# WunderBar_v102b.net
KiCad netlist of a schematic drawn in Altium Designer
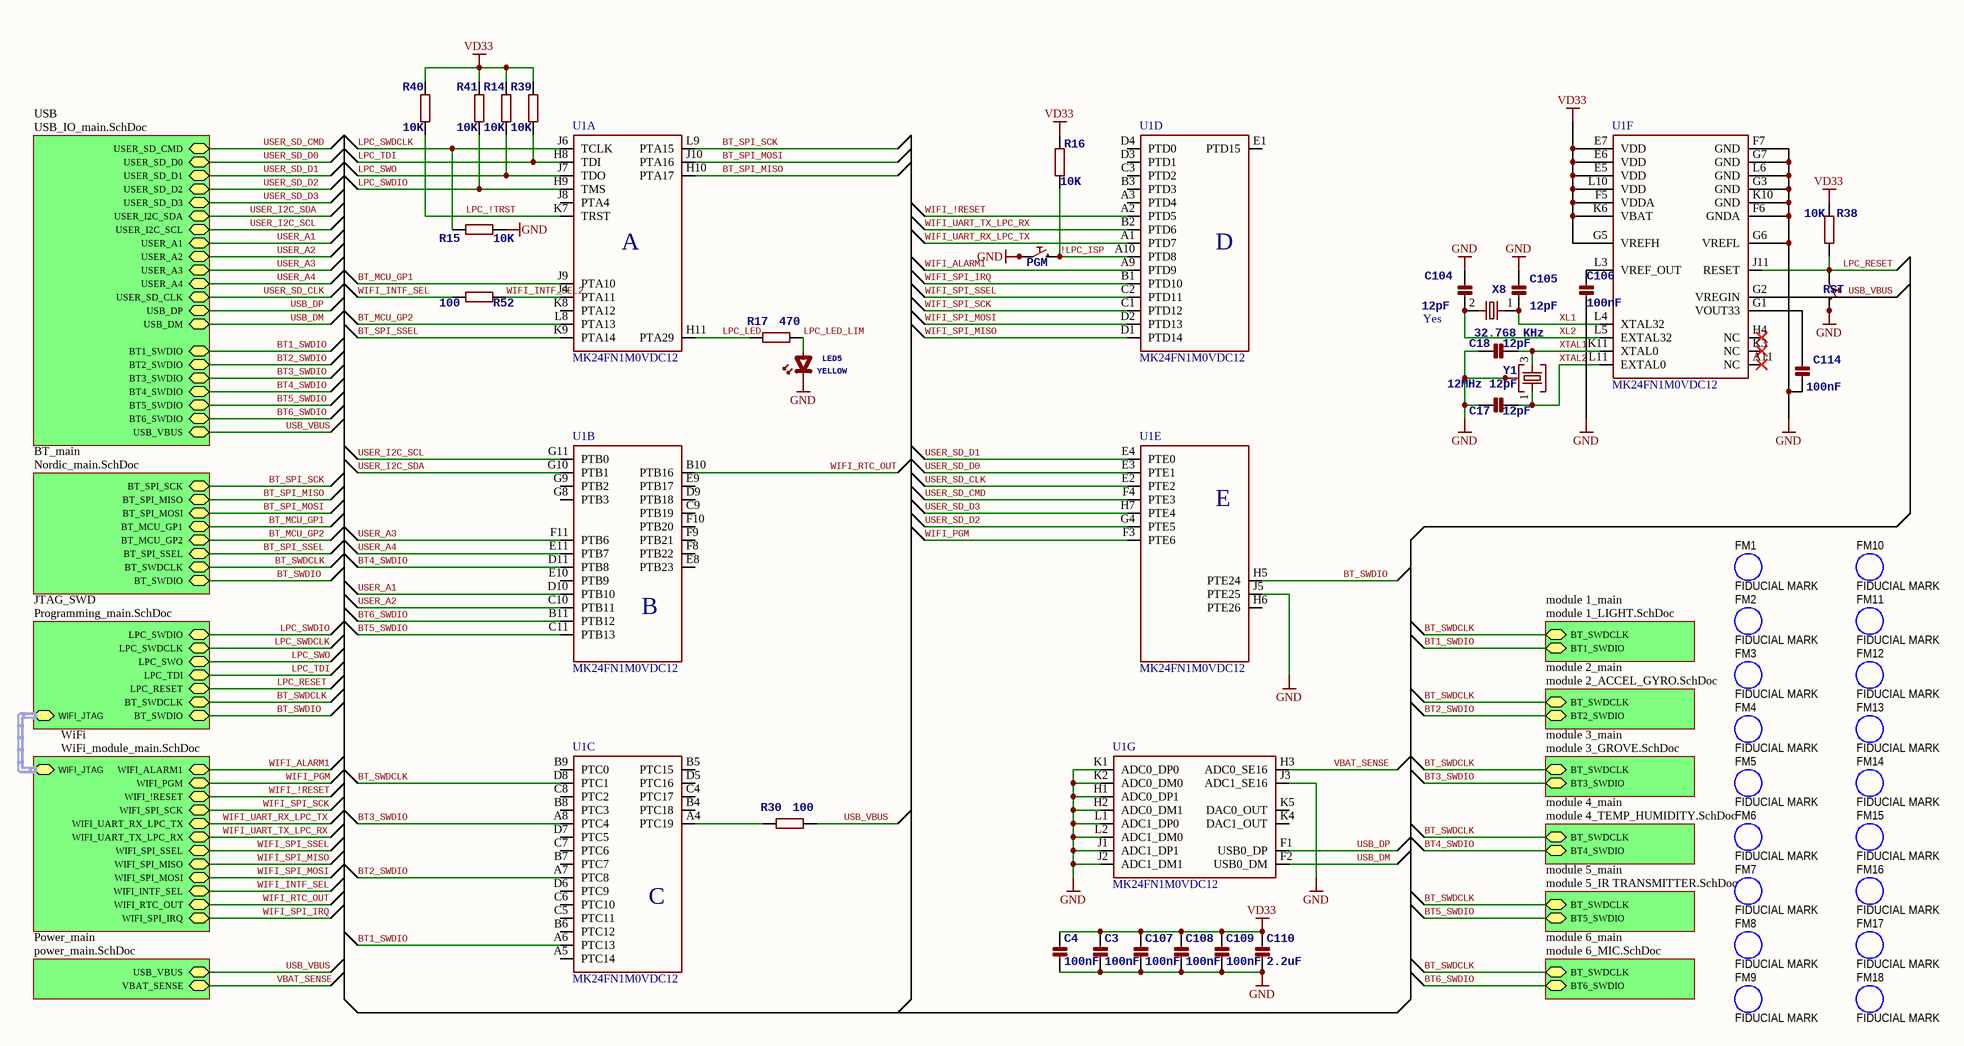
[diagram p0: WunderBar_v102b.SchDoc]

(export (version "E")
  (design (tool "Eeschema 10.0.6"))
  (components
    (comp (ref "C3")
      (value "100nF")
      (footprint "0402")
      (description "Ceramic capacitor")
      (libsource (lib "WunderBar_v101") (part "CAP_CERAMIC0402"))
    )
    (comp (ref "C4")
      (value "100nF")
      (footprint "0402")
      (description "Ceramic capacitor")
      (libsource (lib "WunderBar_v101") (part "CAP_CERAMIC0402"))
    )
    (comp (ref "C17")
      (value "12pF")
      (footprint "0402")
      (description "Ceramic capacitor")
      (libsource (lib "WunderBar_v101") (part "CAP_CERAMIC0402"))
    )
    (comp (ref "C18")
      (value "12pF")
      (footprint "0402")
      (description "Ceramic capacitor")
      (libsource (lib "WunderBar_v101") (part "CAP_CERAMIC0402"))
    )
    (comp (ref "C104")
      (value "12pF")
      (footprint "0402")
      (description "Ceramic capacitor")
      (fields (field (name "SMD") "Yes"))
      (libsource (lib "") (part "CAP_CERAMIC0402_1"))
    )
    (comp (ref "C105")
      (value "12pF")
      (footprint "0402")
      (description "Ceramic capacitor")
      (libsource (lib "") (part "CAP_CERAMIC0402_1"))
    )
    (comp (ref "C106")
      (value "100nF")
      (footprint "0402")
      (description "Ceramic capacitor")
      (libsource (lib "WunderBar_v101") (part "CAP_CERAMIC0402"))
    )
    (comp (ref "C107")
      (value "100nF")
      (footprint "0402")
      (description "Ceramic capacitor")
      (libsource (lib "WunderBar_v101") (part "CAP_CERAMIC0402"))
    )
    (comp (ref "C108")
      (value "100nF")
      (footprint "0402")
      (description "Ceramic capacitor")
      (libsource (lib "WunderBar_v101") (part "CAP_CERAMIC0402"))
    )
    (comp (ref "C109")
      (value "100nF")
      (footprint "0402")
      (description "Ceramic capacitor")
      (libsource (lib "WunderBar_v101") (part "CAP_CERAMIC0402"))
    )
    (comp (ref "C110")
      (value "2.2uF")
      (footprint "0603")
      (description "Ceramic capacitor")
      (libsource (lib "WunderBar_v101") (part "CAP_CERAMIC0402"))
    )
    (comp (ref "C114")
      (value "100nF")
      (footprint "0402")
      (description "Ceramic capacitor")
      (libsource (lib "") (part "CAP_CERAMIC0402_1"))
    )
    (comp (ref "FM1")
      (value "FIDUCIAL MARK")
      (footprint "FIDUCIAL MARK 0.6MM")
      (description "Fiducial Mark")
      (libsource (lib "WunderBar_v101") (part "FIDUCIAL MARK"))
    )
    (comp (ref "FM2")
      (value "FIDUCIAL MARK")
      (footprint "FIDUCIAL MARK 0.6MM")
      (description "Fiducial Mark")
      (libsource (lib "WunderBar_v101") (part "FIDUCIAL MARK"))
    )
    (comp (ref "FM3")
      (value "FIDUCIAL MARK")
      (footprint "FIDUCIAL MARK 0.6MM")
      (description "Fiducial Mark")
      (libsource (lib "WunderBar_v101") (part "FIDUCIAL MARK"))
    )
    (comp (ref "FM4")
      (value "FIDUCIAL MARK")
      (footprint "FIDUCIAL MARK 0.6MM")
      (description "Fiducial Mark")
      (libsource (lib "WunderBar_v101") (part "FIDUCIAL MARK"))
    )
    (comp (ref "FM5")
      (value "FIDUCIAL MARK")
      (footprint "FIDUCIAL MARK 0.6MM")
      (description "Fiducial Mark")
      (libsource (lib "WunderBar_v101") (part "FIDUCIAL MARK"))
    )
    (comp (ref "FM6")
      (value "FIDUCIAL MARK")
      (footprint "FIDUCIAL MARK 0.6MM")
      (description "Fiducial Mark")
      (libsource (lib "WunderBar_v101") (part "FIDUCIAL MARK"))
    )
    (comp (ref "FM7")
      (value "FIDUCIAL MARK")
      (footprint "FIDUCIAL MARK 0.6MM")
      (description "Fiducial Mark")
      (libsource (lib "WunderBar_v101") (part "FIDUCIAL MARK"))
    )
    (comp (ref "FM8")
      (value "FIDUCIAL MARK")
      (footprint "FIDUCIAL MARK 0.6MM")
      (description "Fiducial Mark")
      (libsource (lib "WunderBar_v101") (part "FIDUCIAL MARK"))
    )
    (comp (ref "FM9")
      (value "FIDUCIAL MARK")
      (footprint "FIDUCIAL MARK 0.6MM")
      (description "Fiducial Mark")
      (libsource (lib "WunderBar_v101") (part "FIDUCIAL MARK"))
    )
    (comp (ref "FM10")
      (value "FIDUCIAL MARK")
      (footprint "FIDUCIAL MARK 0.6MM")
      (description "Fiducial Mark")
      (libsource (lib "WunderBar_v101") (part "FIDUCIAL MARK"))
    )
    (comp (ref "FM11")
      (value "FIDUCIAL MARK")
      (footprint "FIDUCIAL MARK 0.6MM")
      (description "Fiducial Mark")
      (libsource (lib "WunderBar_v101") (part "FIDUCIAL MARK"))
    )
    (comp (ref "FM12")
      (value "FIDUCIAL MARK")
      (footprint "FIDUCIAL MARK 0.6MM")
      (description "Fiducial Mark")
      (libsource (lib "WunderBar_v101") (part "FIDUCIAL MARK"))
    )
    (comp (ref "FM13")
      (value "FIDUCIAL MARK")
      (footprint "FIDUCIAL MARK 0.6MM")
      (description "Fiducial Mark")
      (libsource (lib "WunderBar_v101") (part "FIDUCIAL MARK"))
    )
    (comp (ref "FM14")
      (value "FIDUCIAL MARK")
      (footprint "FIDUCIAL MARK 0.6MM")
      (description "Fiducial Mark")
      (libsource (lib "WunderBar_v101") (part "FIDUCIAL MARK"))
    )
    (comp (ref "FM15")
      (value "FIDUCIAL MARK")
      (footprint "FIDUCIAL MARK 0.6MM")
      (description "Fiducial Mark")
      (libsource (lib "WunderBar_v101") (part "FIDUCIAL MARK"))
    )
    (comp (ref "FM16")
      (value "FIDUCIAL MARK")
      (footprint "FIDUCIAL MARK 0.6MM")
      (description "Fiducial Mark")
      (libsource (lib "WunderBar_v101") (part "FIDUCIAL MARK"))
    )
    (comp (ref "FM17")
      (value "FIDUCIAL MARK")
      (footprint "FIDUCIAL MARK 0.6MM")
      (description "Fiducial Mark")
      (libsource (lib "WunderBar_v101") (part "FIDUCIAL MARK"))
    )
    (comp (ref "FM18")
      (value "FIDUCIAL MARK")
      (footprint "FIDUCIAL MARK 0.6MM")
      (description "Fiducial Mark")
      (libsource (lib "WunderBar_v101") (part "FIDUCIAL MARK"))
    )
    (comp (ref "LED5")
      (value "YELLOW")
      (footprint "0402_POLAR")
      (description "LED common")
      (libsource (lib "WunderBar_v101") (part "LED0402"))
    )
    (comp (ref "PGM")
      (value "Tact Sw 4.6x2.8")
      (footprint "CK-KMR2")
      (description "Push button")
      (libsource (lib "WunderBar_v101") (part "PUSHBUTTONKMR2XX"))
    )
    (comp (ref "R14")
      (value "10K")
      (footprint "0402")
      (description "RESISTOR")
      (libsource (lib "WunderBar_v101") (part "R-EU_0402"))
    )
    (comp (ref "R15")
      (value "10K")
      (footprint "0402")
      (description "RESISTOR")
      (libsource (lib "WunderBar_v101") (part "R-EU_0402"))
    )
    (comp (ref "R16")
      (value "10K")
      (footprint "0402")
      (description "RESISTOR")
      (libsource (lib "WunderBar_v101") (part "R-EU_0402"))
    )
    (comp (ref "R17")
      (value "470")
      (footprint "0402")
      (description "RESISTOR")
      (libsource (lib "WunderBar_v101") (part "R-EU_0402"))
    )
    (comp (ref "R30")
      (value "100")
      (footprint "0402")
      (description "RESISTOR")
      (libsource (lib "WunderBar_v101") (part "R-EU_0402"))
    )
    (comp (ref "R38")
      (value "10K")
      (footprint "0402")
      (description "RESISTOR")
      (libsource (lib "WunderBar_v101") (part "R-EU_0402"))
    )
    (comp (ref "R39")
      (value "10K")
      (footprint "0402")
      (description "RESISTOR")
      (libsource (lib "WunderBar_v101") (part "R-EU_0402"))
    )
    (comp (ref "R40")
      (value "10K")
      (footprint "0402")
      (description "RESISTOR")
      (libsource (lib "WunderBar_v101") (part "R-EU_0402"))
    )
    (comp (ref "R41")
      (value "10K")
      (footprint "0402")
      (description "RESISTOR")
      (libsource (lib "WunderBar_v101") (part "R-EU_0402"))
    )
    (comp (ref "R52")
      (value "100")
      (footprint "0402")
      (description "RESISTOR")
      (libsource (lib "WunderBar_v101") (part "R-EU_0402"))
    )
    (comp (ref "RST")
      (value "Tact Sw 4.6x2.8")
      (footprint "CK-KMR2")
      (description "Push button")
      (libsource (lib "WunderBar_v101") (part "PUSHBUTTONKMR2XX"))
    )
    (comp (ref "U1")
      (value "MK24FN1M0VDC12")
      (footprint "BGA121-0.65")
      (description "MK24FN1M0VDC12 121-PIN BGA Microcontroller")
      (libsource (lib "WunderBar_v101") (part "MK24FN1M0VDC12"))
    )
    (comp (ref "X8")
      (value "32.768 KHz")
      (footprint "1206_MINIMELF_COMBO")
      (description "CL05C120JB5")
      (libsource (lib "WunderBar_v101") (part "CRYSTAL1206"))
    )
    (comp (ref "Y1")
      (value "12MHz 12pF")
      (footprint "ABM8G")
      (description "CX2520DB16000D0GEJCC")
      (libsource (lib "WunderBar_v101") (part "CRYSTAL_WITH_GROUNDABM8G"))
    )
  )
  (nets
    (net (code "1") (name "/!LPC_ISP") (class "Default")
      (node (ref "PGM") (pin "P3") (pinfunction "3_P3") (pintype "passive"))
      (node (ref "PGM") (pin "P4") (pinfunction "4_P4") (pintype "passive"))
      (node (ref "R16") (pin "1") (pinfunction "1_1") (pintype "passive"))
      (node (ref "U1") (pin "A10") (pinfunction "PTD8_A10") (pintype "passive"))
    )
    (net (code "2") (name "/BT1_SWDIO") (class "Default")
      (node (ref "U1") (pin "A6") (pinfunction "PTC13_A6") (pintype "passive"))
    )
    (net (code "3") (name "/BT2_SWDIO") (class "Default")
      (node (ref "U1") (pin "A7") (pinfunction "PTC8_A7") (pintype "passive"))
    )
    (net (code "4") (name "/BT3_SWDIO") (class "Default")
      (node (ref "U1") (pin "A8") (pinfunction "PTC4_A8") (pintype "passive"))
    )
    (net (code "5") (name "/BT4_SWDIO") (class "Default")
      (node (ref "U1") (pin "D11") (pinfunction "PTB8_D11") (pintype "passive"))
    )
    (net (code "6") (name "/BT5_SWDIO") (class "Default")
      (node (ref "U1") (pin "C11") (pinfunction "PTB13_C11") (pintype "passive"))
    )
    (net (code "7") (name "/BT6_SWDIO") (class "Default")
      (node (ref "U1") (pin "B11") (pinfunction "PTB12_B11") (pintype "passive"))
    )
    (net (code "8") (name "/BT_MCU_GP1") (class "Default")
      (node (ref "U1") (pin "J9") (pinfunction "PTA10_J9") (pintype "passive"))
    )
    (net (code "9") (name "/BT_MCU_GP2") (class "Default")
      (node (ref "U1") (pin "L8") (pinfunction "PTA13_L8") (pintype "passive"))
    )
    (net (code "10") (name "/BT_SPI_MISO") (class "Default")
      (node (ref "U1") (pin "H10") (pinfunction "PTA17_H10") (pintype "passive"))
    )
    (net (code "11") (name "/BT_SPI_MOSI") (class "Default")
      (node (ref "U1") (pin "J10") (pinfunction "PTA16_J10") (pintype "passive"))
    )
    (net (code "12") (name "/BT_SPI_SCK") (class "Default")
      (node (ref "U1") (pin "L9") (pinfunction "PTA15_L9") (pintype "passive"))
    )
    (net (code "13") (name "/BT_SPI_SSEL") (class "Default")
      (node (ref "U1") (pin "K9") (pinfunction "PTA14_K9") (pintype "passive"))
    )
    (net (code "14") (name "/BT_SWDCLK") (class "Default")
      (node (ref "U1") (pin "D8") (pinfunction "PTC1_D8") (pintype "passive"))
    )
    (net (code "15") (name "/BT_SWDIO") (class "Default")
      (node (ref "U1") (pin "H5") (pinfunction "PTE24_H5") (pintype "passive"))
    )
    (net (code "16") (name "/LPC_!TRST") (class "Default")
      (node (ref "R40") (pin "1") (pinfunction "1_1") (pintype "passive"))
      (node (ref "U1") (pin "K7") (pinfunction "TRST_K7") (pintype "passive"))
    )
    (net (code "17") (name "/LPC_LED") (class "Default")
      (node (ref "R17") (pin "2") (pinfunction "2_2") (pintype "passive"))
      (node (ref "U1") (pin "H11") (pinfunction "PTA29_H11") (pintype "passive"))
    )
    (net (code "18") (name "/LPC_LED_LIM") (class "Default")
      (node (ref "LED5") (pin "A") (pinfunction "ANODE_A") (pintype "passive"))
      (node (ref "R17") (pin "1") (pinfunction "1_1") (pintype "passive"))
    )
    (net (code "19") (name "/LPC_RESET") (class "Default")
      (node (ref "R38") (pin "1") (pinfunction "1_1") (pintype "passive"))
      (node (ref "RST") (pin "P1") (pinfunction "1_P1") (pintype "passive"))
      (node (ref "RST") (pin "P2") (pinfunction "2_P2") (pintype "passive"))
      (node (ref "U1") (pin "J11") (pinfunction "RESET_J11") (pintype "passive"))
    )
    (net (code "20") (name "/LPC_SWDCLK") (class "Default")
      (node (ref "R15") (pin "1") (pinfunction "1_1") (pintype "passive"))
      (node (ref "U1") (pin "J6") (pinfunction "TCLK_J6") (pintype "passive"))
    )
    (net (code "21") (name "/LPC_SWDIO") (class "Default")
      (node (ref "R41") (pin "1") (pinfunction "1_1") (pintype "passive"))
      (node (ref "U1") (pin "H9") (pinfunction "TMS_H9") (pintype "passive"))
    )
    (net (code "22") (name "/LPC_SWO") (class "Default")
      (node (ref "R14") (pin "1") (pinfunction "1_1") (pintype "passive"))
      (node (ref "U1") (pin "J7") (pinfunction "TDO_J7") (pintype "passive"))
    )
    (net (code "23") (name "/LPC_TDI") (class "Default")
      (node (ref "R39") (pin "1") (pinfunction "1_1") (pintype "passive"))
      (node (ref "U1") (pin "H8") (pinfunction "TDI_H8") (pintype "passive"))
    )
    (net (code "24") (name "/USB_DM") (class "Default")
      (node (ref "U1") (pin "F2") (pinfunction "USB0_DM_F2") (pintype "passive"))
    )
    (net (code "25") (name "/USB_DP") (class "Default")
      (node (ref "U1") (pin "F1") (pinfunction "USB0_DP_F1") (pintype "passive"))
    )
    (net (code "26") (name "/USB_VBUS") (class "Default")
      (node (ref "R30") (pin "1") (pinfunction "1_1") (pintype "passive"))
      (node (ref "U1") (pin "G2") (pinfunction "VREGIN_G2") (pintype "passive"))
    )
    (net (code "27") (name "/USER_A1") (class "Default")
      (node (ref "U1") (pin "D10") (pinfunction "PTB10_D10") (pintype "passive"))
    )
    (net (code "28") (name "/USER_A2") (class "Default")
      (node (ref "U1") (pin "C10") (pinfunction "PTB11_C10") (pintype "passive"))
    )
    (net (code "29") (name "/USER_A3") (class "Default")
      (node (ref "U1") (pin "F11") (pinfunction "PTB6_F11") (pintype "passive"))
    )
    (net (code "30") (name "/USER_A4") (class "Default")
      (node (ref "U1") (pin "E11") (pinfunction "PTB7_E11") (pintype "passive"))
    )
    (net (code "31") (name "/USER_I2C_SCL") (class "Default")
      (node (ref "U1") (pin "G11") (pinfunction "PTB0_G11") (pintype "passive"))
    )
    (net (code "32") (name "/USER_I2C_SDA") (class "Default")
      (node (ref "U1") (pin "G10") (pinfunction "PTB1_G10") (pintype "passive"))
    )
    (net (code "33") (name "/USER_SD_CLK") (class "Default")
      (node (ref "U1") (pin "E2") (pinfunction "PTE2_E2") (pintype "passive"))
    )
    (net (code "34") (name "/USER_SD_CMD") (class "Default")
      (node (ref "U1") (pin "F4") (pinfunction "PTE3_F4") (pintype "passive"))
    )
    (net (code "35") (name "/USER_SD_D0") (class "Default")
      (node (ref "U1") (pin "E3") (pinfunction "PTE1_E3") (pintype "passive"))
    )
    (net (code "36") (name "/USER_SD_D1") (class "Default")
      (node (ref "U1") (pin "E4") (pinfunction "PTE0_E4") (pintype "passive"))
    )
    (net (code "37") (name "/USER_SD_D2") (class "Default")
      (node (ref "U1") (pin "G4") (pinfunction "PTE5_G4") (pintype "passive"))
    )
    (net (code "38") (name "/USER_SD_D3") (class "Default")
      (node (ref "U1") (pin "H7") (pinfunction "PTE4_H7") (pintype "passive"))
    )
    (net (code "39") (name "/VBAT_SENSE") (class "Default")
      (node (ref "U1") (pin "H3") (pinfunction "ADC0_SE16_H3") (pintype "passive"))
    )
    (net (code "40") (name "/WIFI_!RESET") (class "Default")
      (node (ref "U1") (pin "A2") (pinfunction "PTD5_A2") (pintype "passive"))
    )
    (net (code "41") (name "/WIFI_ALARM1") (class "Default")
      (node (ref "U1") (pin "A9") (pinfunction "PTD9_A9") (pintype "passive"))
    )
    (net (code "42") (name "/WIFI_INTF_SEL") (class "Default")
      (node (ref "R52") (pin "1") (pinfunction "1_1") (pintype "passive"))
    )
    (net (code "43") (name "/WIFI_INTF_SEL2") (class "Default")
      (node (ref "R52") (pin "2") (pinfunction "2_2") (pintype "passive"))
      (node (ref "U1") (pin "J4") (pinfunction "PTA11_J4") (pintype "passive"))
    )
    (net (code "45") (name "/WIFI_PGM") (class "Default")
      (node (ref "U1") (pin "F3") (pinfunction "PTE6_F3") (pintype "passive"))
    )
    (net (code "46") (name "/WIFI_RTC_OUT") (class "Default")
      (node (ref "U1") (pin "B10") (pinfunction "PTB16_B10") (pintype "passive"))
    )
    (net (code "47") (name "/WIFI_SPI_IRQ") (class "Default")
      (node (ref "U1") (pin "B1") (pinfunction "PTD10_B1") (pintype "passive"))
    )
    (net (code "48") (name "/WIFI_SPI_MISO") (class "Default")
      (node (ref "U1") (pin "D1") (pinfunction "PTD14_D1") (pintype "passive"))
    )
    (net (code "49") (name "/WIFI_SPI_MOSI") (class "Default")
      (node (ref "U1") (pin "D2") (pinfunction "PTD13_D2") (pintype "passive"))
    )
    (net (code "50") (name "/WIFI_SPI_SCK") (class "Default")
      (node (ref "U1") (pin "C1") (pinfunction "PTD12_C1") (pintype "passive"))
    )
    (net (code "51") (name "/WIFI_SPI_SSEL") (class "Default")
      (node (ref "U1") (pin "C2") (pinfunction "PTD11_C2") (pintype "passive"))
    )
    (net (code "52") (name "/WIFI_UART_RX_LPC_TX") (class "Default")
      (node (ref "U1") (pin "A1") (pinfunction "PTD7_A1") (pintype "passive"))
    )
    (net (code "53") (name "/WIFI_UART_TX_LPC_RX") (class "Default")
      (node (ref "U1") (pin "B2") (pinfunction "PTD6_B2") (pintype "passive"))
    )
    (net (code "54") (name "/XL1") (class "Default")
      (node (ref "C105") (pin "1") (pinfunction "1_1") (pintype "passive"))
      (node (ref "U1") (pin "L4") (pinfunction "XTAL32_L4") (pintype "passive"))
      (node (ref "X8") (pin "1") (pinfunction "1_1") (pintype "passive"))
    )
    (net (code "55") (name "/XL2") (class "Default")
      (node (ref "C104") (pin "1") (pinfunction "1_1") (pintype "passive"))
      (node (ref "U1") (pin "L5") (pinfunction "EXTAL32_L5") (pintype "passive"))
      (node (ref "X8") (pin "2") (pinfunction "2_2") (pintype "passive"))
    )
    (net (code "56") (name "/XTAL1") (class "Default")
      (node (ref "C18") (pin "1") (pinfunction "1_1") (pintype "passive"))
      (node (ref "U1") (pin "K11") (pinfunction "XTAL0_K11") (pintype "passive"))
      (node (ref "Y1") (pin "3") (pinfunction "2_3") (pintype "passive"))
    )
    (net (code "57") (name "/XTAL2") (class "Default")
      (node (ref "C17") (pin "1") (pinfunction "1_1") (pintype "passive"))
      (node (ref "U1") (pin "L11") (pinfunction "EXTAL0_L11") (pintype "passive"))
      (node (ref "Y1") (pin "1") (pinfunction "1_1") (pintype "passive"))
    )
    (net (code "58") (name "GND") (class "Default")
      (node (ref "C104") (pin "2") (pinfunction "2_2") (pintype "passive"))
      (node (ref "C105") (pin "2") (pinfunction "2_2") (pintype "passive"))
      (node (ref "C106") (pin "2") (pinfunction "2_2") (pintype "passive"))
      (node (ref "C107") (pin "2") (pinfunction "2_2") (pintype "passive"))
      (node (ref "C108") (pin "2") (pinfunction "2_2") (pintype "passive"))
      (node (ref "C109") (pin "2") (pinfunction "2_2") (pintype "passive"))
      (node (ref "C110") (pin "2") (pinfunction "2_2") (pintype "passive"))
      (node (ref "C114") (pin "1") (pinfunction "1_1") (pintype "passive"))
      (node (ref "C17") (pin "2") (pinfunction "2_2") (pintype "passive"))
      (node (ref "C18") (pin "2") (pinfunction "2_2") (pintype "passive"))
      (node (ref "C3") (pin "2") (pinfunction "2_2") (pintype "passive"))
      (node (ref "C4") (pin "2") (pinfunction "2_2") (pintype "passive"))
      (node (ref "LED5") (pin "K") (pinfunction "CATHODE_K") (pintype "passive"))
      (node (ref "PGM") (pin "P1") (pinfunction "1_P1") (pintype "passive"))
      (node (ref "PGM") (pin "P2") (pinfunction "2_P2") (pintype "passive"))
      (node (ref "R15") (pin "2") (pinfunction "2_2") (pintype "passive"))
      (node (ref "RST") (pin "P3") (pinfunction "3_P3") (pintype "passive"))
      (node (ref "RST") (pin "P4") (pinfunction "4_P4") (pintype "passive"))
      (node (ref "U1") (pin "F6") (pinfunction "GNDA_F6") (pintype "passive"))
      (node (ref "U1") (pin "F7") (pinfunction "GND_F7") (pintype "passive"))
      (node (ref "U1") (pin "G3") (pinfunction "GND_G3") (pintype "passive"))
      (node (ref "U1") (pin "G6") (pinfunction "VREFL_G6") (pintype "passive"))
      (node (ref "U1") (pin "G7") (pinfunction "GND_G7") (pintype "passive"))
      (node (ref "U1") (pin "H1") (pinfunction "ADC0_DP1_H1") (pintype "passive"))
      (node (ref "U1") (pin "H2") (pinfunction "ADC0_DM1_H2") (pintype "passive"))
      (node (ref "U1") (pin "J1") (pinfunction "ADC1_DP1_J1") (pintype "passive"))
      (node (ref "U1") (pin "J2") (pinfunction "ADC1_DM1_J2") (pintype "passive"))
      (node (ref "U1") (pin "J3") (pinfunction "ADC1_SE16_J3") (pintype "passive"))
      (node (ref "U1") (pin "J5") (pinfunction "PTE25_J5") (pintype "passive"))
      (node (ref "U1") (pin "K1") (pinfunction "ADC0_DP0_K1") (pintype "passive"))
      (node (ref "U1") (pin "K10") (pinfunction "GND_K10") (pintype "passive"))
      (node (ref "U1") (pin "K2") (pinfunction "ADC0_DM0_K2") (pintype "passive"))
      (node (ref "U1") (pin "L1") (pinfunction "ADC1_DP0_L1") (pintype "passive"))
      (node (ref "U1") (pin "L2") (pinfunction "ADC1_DM0_L2") (pintype "passive"))
      (node (ref "U1") (pin "L6") (pinfunction "GND_L6") (pintype "passive"))
      (node (ref "Y1") (pin "2") (pinfunction "GND_2") (pintype "power_in"))
      (node (ref "Y1") (pin "4") (pinfunction "GND_4") (pintype "power_in"))
    )
    (net (code "59") (name "Net-(U1C-PTC19)") (class "Default")
      (node (ref "R30") (pin "2") (pinfunction "2_2") (pintype "passive"))
      (node (ref "U1") (pin "A4") (pinfunction "PTC19_A4") (pintype "passive"))
    )
    (net (code "60") (name "Net-(U1F-VOUT33)") (class "Default")
      (node (ref "C114") (pin "2") (pinfunction "2_2") (pintype "passive"))
      (node (ref "U1") (pin "G1") (pinfunction "VOUT33_G1") (pintype "passive"))
    )
    (net (code "61") (name "Net-(U1F-VREF_OUT)") (class "Default")
      (node (ref "C106") (pin "1") (pinfunction "1_1") (pintype "passive"))
      (node (ref "U1") (pin "L3") (pinfunction "VREF_OUT_L3") (pintype "passive"))
    )
    (net (code "62") (name "VD33") (class "Default")
      (node (ref "C107") (pin "1") (pinfunction "1_1") (pintype "passive"))
      (node (ref "C108") (pin "1") (pinfunction "1_1") (pintype "passive"))
      (node (ref "C109") (pin "1") (pinfunction "1_1") (pintype "passive"))
      (node (ref "C110") (pin "1") (pinfunction "1_1") (pintype "passive"))
      (node (ref "C3") (pin "1") (pinfunction "1_1") (pintype "passive"))
      (node (ref "C4") (pin "1") (pinfunction "1_1") (pintype "passive"))
      (node (ref "R14") (pin "2") (pinfunction "2_2") (pintype "passive"))
      (node (ref "R16") (pin "2") (pinfunction "2_2") (pintype "passive"))
      (node (ref "R38") (pin "2") (pinfunction "2_2") (pintype "passive"))
      (node (ref "R39") (pin "2") (pinfunction "2_2") (pintype "passive"))
      (node (ref "R40") (pin "2") (pinfunction "2_2") (pintype "passive"))
      (node (ref "R41") (pin "2") (pinfunction "2_2") (pintype "passive"))
      (node (ref "U1") (pin "E5") (pinfunction "VDD_E5") (pintype "passive"))
      (node (ref "U1") (pin "E6") (pinfunction "VDD_E6") (pintype "passive"))
      (node (ref "U1") (pin "E7") (pinfunction "VDD_E7") (pintype "passive"))
      (node (ref "U1") (pin "F5") (pinfunction "VDDA_F5") (pintype "passive"))
      (node (ref "U1") (pin "G5") (pinfunction "VREFH_G5") (pintype "passive"))
      (node (ref "U1") (pin "K6") (pinfunction "VBAT_K6") (pintype "passive"))
      (node (ref "U1") (pin "L10") (pinfunction "VDD_L10") (pintype "passive"))
    )
    (net (code "63") (name "unconnected-(U1A-PTA4-PadJ8)") (class "Default")
      (node (ref "U1") (pin "J8") (pinfunction "PTA4_J8") (pintype "passive"))
    )
    (net (code "64") (name "unconnected-(U1A-PTA12-PadK8)") (class "Default")
      (node (ref "U1") (pin "K8") (pinfunction "PTA12_K8") (pintype "passive"))
    )
    (net (code "65") (name "unconnected-(U1B-PTB2-PadG9)") (class "Default")
      (node (ref "U1") (pin "G9") (pinfunction "PTB2_G9") (pintype "passive"))
    )
    (net (code "66") (name "unconnected-(U1B-PTB3-PadG8)") (class "Default")
      (node (ref "U1") (pin "G8") (pinfunction "PTB3_G8") (pintype "passive"))
    )
    (net (code "67") (name "unconnected-(U1B-PTB9-PadE10)") (class "Default")
      (node (ref "U1") (pin "E10") (pinfunction "PTB9_E10") (pintype "passive"))
    )
    (net (code "68") (name "unconnected-(U1B-PTB17-PadE9)") (class "Default")
      (node (ref "U1") (pin "E9") (pinfunction "PTB17_E9") (pintype "passive"))
    )
    (net (code "69") (name "unconnected-(U1B-PTB18-PadD9)") (class "Default")
      (node (ref "U1") (pin "D9") (pinfunction "PTB18_D9") (pintype "passive"))
    )
    (net (code "70") (name "unconnected-(U1B-PTB19-PadC9)") (class "Default")
      (node (ref "U1") (pin "C9") (pinfunction "PTB19_C9") (pintype "passive"))
    )
    (net (code "71") (name "unconnected-(U1B-PTB20-PadF10)") (class "Default")
      (node (ref "U1") (pin "F10") (pinfunction "PTB20_F10") (pintype "passive"))
    )
    (net (code "72") (name "unconnected-(U1B-PTB21-PadF9)") (class "Default")
      (node (ref "U1") (pin "F9") (pinfunction "PTB21_F9") (pintype "passive"))
    )
    (net (code "73") (name "unconnected-(U1B-PTB22-PadF8)") (class "Default")
      (node (ref "U1") (pin "F8") (pinfunction "PTB22_F8") (pintype "passive"))
    )
    (net (code "74") (name "unconnected-(U1B-PTB23-PadE8)") (class "Default")
      (node (ref "U1") (pin "E8") (pinfunction "PTB23_E8") (pintype "passive"))
    )
    (net (code "75") (name "unconnected-(U1C-PTC0-PadB9)") (class "Default")
      (node (ref "U1") (pin "B9") (pinfunction "PTC0_B9") (pintype "passive"))
    )
    (net (code "76") (name "unconnected-(U1C-PTC2-PadC8)") (class "Default")
      (node (ref "U1") (pin "C8") (pinfunction "PTC2_C8") (pintype "passive"))
    )
    (net (code "77") (name "unconnected-(U1C-PTC3-PadB8)") (class "Default")
      (node (ref "U1") (pin "B8") (pinfunction "PTC3_B8") (pintype "passive"))
    )
    (net (code "78") (name "unconnected-(U1C-PTC5-PadD7)") (class "Default")
      (node (ref "U1") (pin "D7") (pinfunction "PTC5_D7") (pintype "passive"))
    )
    (net (code "79") (name "unconnected-(U1C-PTC6-PadC7)") (class "Default")
      (node (ref "U1") (pin "C7") (pinfunction "PTC6_C7") (pintype "passive"))
    )
    (net (code "80") (name "unconnected-(U1C-PTC7-PadB7)") (class "Default")
      (node (ref "U1") (pin "B7") (pinfunction "PTC7_B7") (pintype "passive"))
    )
    (net (code "81") (name "unconnected-(U1C-PTC9-PadD6)") (class "Default")
      (node (ref "U1") (pin "D6") (pinfunction "PTC9_D6") (pintype "passive"))
    )
    (net (code "82") (name "unconnected-(U1C-PTC10-PadC6)") (class "Default")
      (node (ref "U1") (pin "C6") (pinfunction "PTC10_C6") (pintype "passive"))
    )
    (net (code "83") (name "unconnected-(U1C-PTC11-PadC5)") (class "Default")
      (node (ref "U1") (pin "C5") (pinfunction "PTC11_C5") (pintype "passive"))
    )
    (net (code "84") (name "unconnected-(U1C-PTC12-PadB6)") (class "Default")
      (node (ref "U1") (pin "B6") (pinfunction "PTC12_B6") (pintype "passive"))
    )
    (net (code "85") (name "unconnected-(U1C-PTC14-PadA5)") (class "Default")
      (node (ref "U1") (pin "A5") (pinfunction "PTC14_A5") (pintype "passive"))
    )
    (net (code "86") (name "unconnected-(U1C-PTC15-PadB5)") (class "Default")
      (node (ref "U1") (pin "B5") (pinfunction "PTC15_B5") (pintype "passive"))
    )
    (net (code "87") (name "unconnected-(U1C-PTC16-PadD5)") (class "Default")
      (node (ref "U1") (pin "D5") (pinfunction "PTC16_D5") (pintype "passive"))
    )
    (net (code "88") (name "unconnected-(U1C-PTC17-PadC4)") (class "Default")
      (node (ref "U1") (pin "C4") (pinfunction "PTC17_C4") (pintype "passive"))
    )
    (net (code "89") (name "unconnected-(U1C-PTC18-PadB4)") (class "Default")
      (node (ref "U1") (pin "B4") (pinfunction "PTC18_B4") (pintype "passive"))
    )
    (net (code "90") (name "unconnected-(U1D-PTD0-PadD4)") (class "Default")
      (node (ref "U1") (pin "D4") (pinfunction "PTD0_D4") (pintype "passive"))
    )
    (net (code "91") (name "unconnected-(U1D-PTD1-PadD3)") (class "Default")
      (node (ref "U1") (pin "D3") (pinfunction "PTD1_D3") (pintype "passive"))
    )
    (net (code "92") (name "unconnected-(U1D-PTD2-PadC3)") (class "Default")
      (node (ref "U1") (pin "C3") (pinfunction "PTD2_C3") (pintype "passive"))
    )
    (net (code "93") (name "unconnected-(U1D-PTD3-PadB3)") (class "Default")
      (node (ref "U1") (pin "B3") (pinfunction "PTD3_B3") (pintype "passive"))
    )
    (net (code "94") (name "unconnected-(U1D-PTD4-PadA3)") (class "Default")
      (node (ref "U1") (pin "A3") (pinfunction "PTD4_A3") (pintype "passive"))
    )
    (net (code "95") (name "unconnected-(U1D-PTD15-PadE1)") (class "Default")
      (node (ref "U1") (pin "E1") (pinfunction "PTD15_E1") (pintype "passive"))
    )
    (net (code "96") (name "unconnected-(U1E-PTE26-PadH6)") (class "Default")
      (node (ref "U1") (pin "H6") (pinfunction "PTE26_H6") (pintype "passive"))
    )
    (net (code "97") (name "unconnected-(U1F-NC-PadA11)") (class "Default")
      (node (ref "U1") (pin "A11") (pinfunction "NC_A11") (pintype "passive+no_connect"))
    )
    (net (code "98") (name "unconnected-(U1F-NC-PadH4)") (class "Default")
      (node (ref "U1") (pin "H4") (pinfunction "NC_H4") (pintype "passive+no_connect"))
    )
    (net (code "99") (name "unconnected-(U1F-NC-PadK3)") (class "Default")
      (node (ref "U1") (pin "K3") (pinfunction "NC_K3") (pintype "passive+no_connect"))
    )
    (net (code "100") (name "unconnected-(U1G-DAC0_OUT-PadK5)") (class "Default")
      (node (ref "U1") (pin "K5") (pinfunction "DAC0_OUT_K5") (pintype "passive"))
    )
    (net (code "101") (name "unconnected-(U1G-DAC1_OUT-PadK4)") (class "Default")
      (node (ref "U1") (pin "K4") (pinfunction "DAC1_OUT_K4") (pintype "passive"))
    )
  )
)
